# STM32F401CCU6.net
KiCad netlist of a schematic drawn in Altium Designer
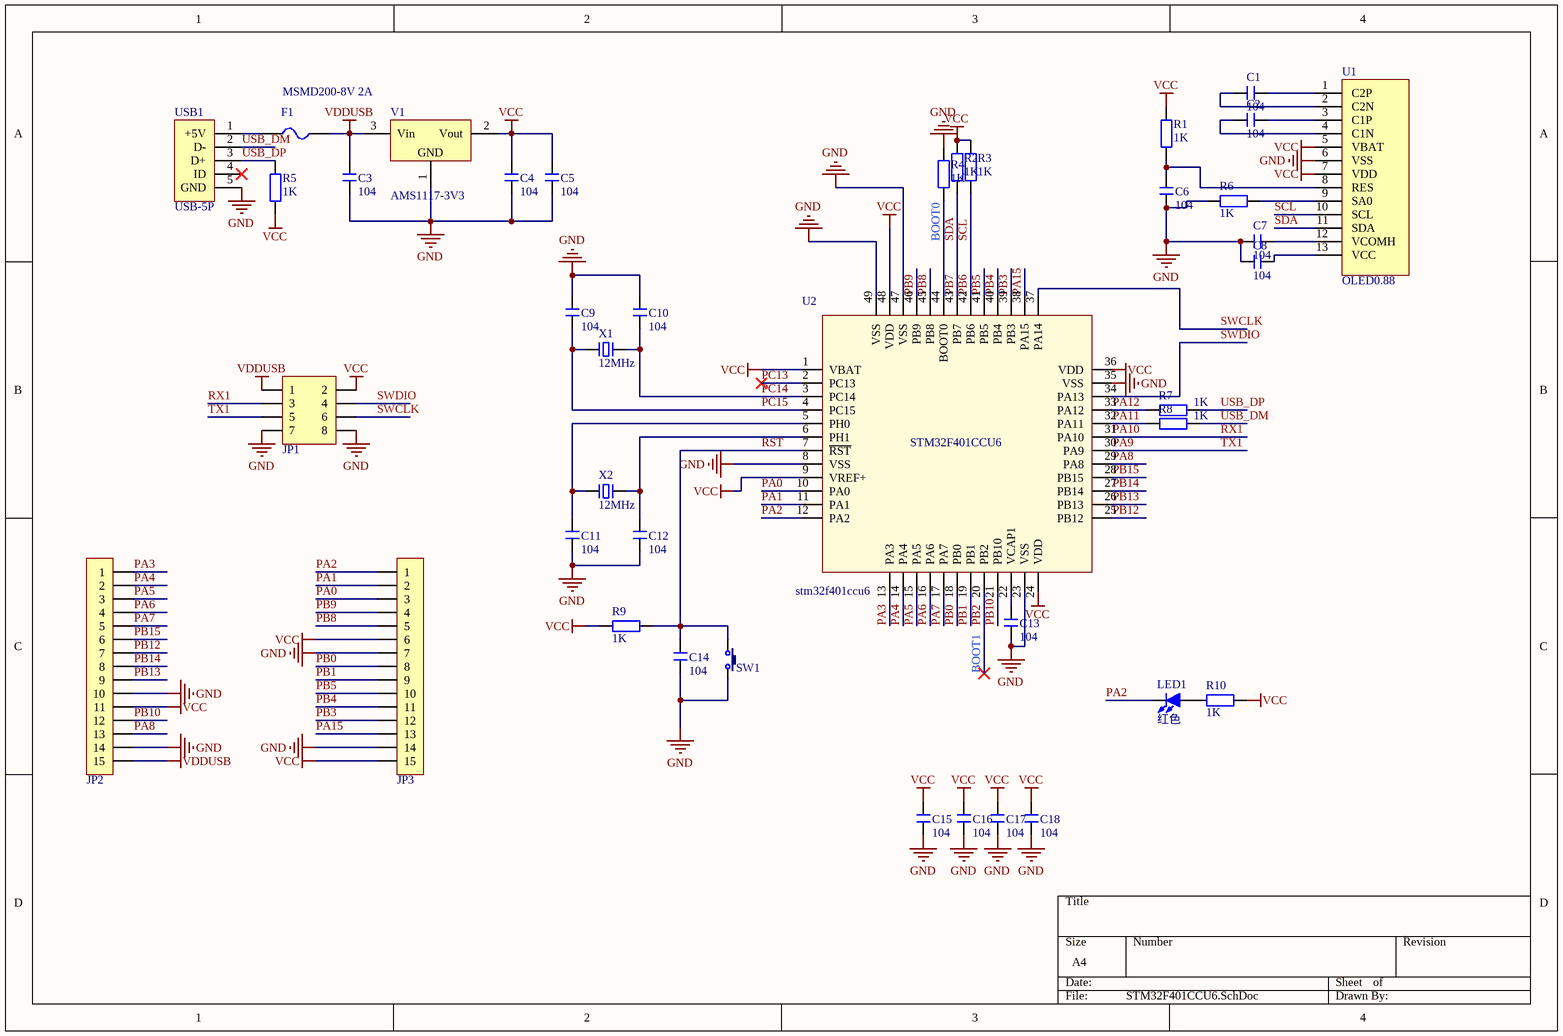
[diagram p0: STM32F401CCU6.SchDoc]

(export (version "E")
  (design (tool "Eeschema 10.0.6"))
  (components
    (comp (ref "C1")
      (value "104")
      (footprint "C 0603_L")
      (description "无极性贴片电容")
      (fields (field (name "版权归属") "源创客"))
      (libsource (lib "3.1   - 电阻-电容-电感") (part "C"))
    )
    (comp (ref "C2")
      (value "104")
      (footprint "C 0603_L")
      (description "无极性贴片电容")
      (fields (field (name "版权归属") "源创客"))
      (libsource (lib "3.1   - 电阻-电容-电感") (part "C"))
    )
    (comp (ref "C3")
      (value "104")
      (footprint "C 0805_L")
      (description "无极性贴片电容")
      (fields (field (name "版权归属") "源创客"))
      (libsource (lib "3.1   - 电阻-电容-电感") (part "C"))
    )
    (comp (ref "C4")
      (value "104")
      (footprint "C 0603_L")
      (description "无极性贴片电容")
      (fields (field (name "版权归属") "源创客"))
      (libsource (lib "3.1   - 电阻-电容-电感") (part "C"))
    )
    (comp (ref "C5")
      (value "104")
      (footprint "C 0603_L")
      (description "无极性贴片电容")
      (fields (field (name "版权归属") "源创客"))
      (libsource (lib "3.1   - 电阻-电容-电感") (part "C"))
    )
    (comp (ref "C6")
      (value "104")
      (footprint "C 0603_L")
      (description "无极性贴片电容")
      (fields (field (name "版权归属") "源创客"))
      (libsource (lib "3.1   - 电阻-电容-电感") (part "C"))
    )
    (comp (ref "C7")
      (value "104")
      (footprint "C 0603_L")
      (description "无极性贴片电容")
      (fields (field (name "版权归属") "源创客"))
      (libsource (lib "3.1   - 电阻-电容-电感") (part "C"))
    )
    (comp (ref "C8")
      (value "104")
      (footprint "C 0603_L")
      (description "无极性贴片电容")
      (fields (field (name "版权归属") "源创客"))
      (libsource (lib "3.1   - 电阻-电容-电感") (part "C"))
    )
    (comp (ref "C9")
      (value "104")
      (footprint "C 0603_L")
      (description "无极性贴片电容")
      (fields (field (name "版权归属") "源创客"))
      (libsource (lib "3.1   - 电阻-电容-电感") (part "C"))
    )
    (comp (ref "C10")
      (value "104")
      (footprint "C 0603_L")
      (description "无极性贴片电容")
      (fields (field (name "版权归属") "源创客"))
      (libsource (lib "3.1   - 电阻-电容-电感") (part "C"))
    )
    (comp (ref "C11")
      (value "104")
      (footprint "C 0603_L")
      (description "无极性贴片电容")
      (fields (field (name "版权归属") "源创客"))
      (libsource (lib "3.1   - 电阻-电容-电感") (part "C"))
    )
    (comp (ref "C12")
      (value "104")
      (footprint "C 0603_L")
      (description "无极性贴片电容")
      (fields (field (name "版权归属") "源创客"))
      (libsource (lib "3.1   - 电阻-电容-电感") (part "C"))
    )
    (comp (ref "C13")
      (value "104")
      (footprint "C 0603_L")
      (description "无极性贴片电容")
      (fields (field (name "版权归属") "源创客"))
      (libsource (lib "3.1   - 电阻-电容-电感") (part "C"))
    )
    (comp (ref "C14")
      (value "104")
      (footprint "C 0603_L")
      (description "无极性贴片电容")
      (fields (field (name "版权归属") "源创客"))
      (libsource (lib "3.1   - 电阻-电容-电感") (part "C"))
    )
    (comp (ref "C15")
      (value "104")
      (footprint "C 0603_L")
      (description "无极性贴片电容")
      (fields (field (name "版权归属") "源创客"))
      (libsource (lib "3.1   - 电阻-电容-电感") (part "C"))
    )
    (comp (ref "C16")
      (value "104")
      (footprint "C 0603_L")
      (description "无极性贴片电容")
      (fields (field (name "版权归属") "源创客"))
      (libsource (lib "3.1   - 电阻-电容-电感") (part "C"))
    )
    (comp (ref "C17")
      (value "104")
      (footprint "C 0603_L")
      (description "无极性贴片电容")
      (fields (field (name "版权归属") "源创客"))
      (libsource (lib "3.1   - 电阻-电容-电感") (part "C"))
    )
    (comp (ref "C18")
      (value "104")
      (footprint "C 0603_L")
      (description "无极性贴片电容")
      (fields (field (name "版权归属") "源创客"))
      (libsource (lib "3.1   - 电阻-电容-电感") (part "C"))
    )
    (comp (ref "F1")
      (value "MSMD200-8V 2A")
      (footprint "FU 0603")
      (description "贴片保险丝")
      (fields (field (name "版权归属") "源创客"))
      (libsource (lib "10.1 - 保险丝-晶振") (part "FU"))
    )
    (comp (ref "JP1")
      (value "Header 4X2")
      (footprint "HDR2.54-WI-2x4P")
      (description "4*2P接插件")
      (fields (field (name "版权归属") "源创客"))
      (libsource (lib "4.5   - 接插件-脚距2.54") (part "Header 4X2"))
    )
    (comp (ref "JP2")
      (value "HDR-1X15")
      (footprint "HDR2.54-LI-15P")
      (description "15P接插件")
      (fields (field (name "版权归属") "源创客"))
      (libsource (lib "4.5   - 接插件-脚距2.54") (part "Header 15"))
    )
    (comp (ref "JP3")
      (value "HDR-1X15")
      (footprint "HDR2.54-LI-15P")
      (description "15P接插件")
      (fields (field (name "版权归属") "源创客"))
      (libsource (lib "") (part "Header 15_1"))
    )
    (comp (ref "LED1")
      (value "红色")
      (footprint "LED 0603Y")
      (description "贴片LED")
      (fields (field (name "版权归属") "源创客"))
      (libsource (lib "9.1   - LED") (part "LED-SMD"))
    )
    (comp (ref "R1")
      (value "1K")
      (footprint "R 0603_L")
      (description "贴片电阻")
      (fields (field (name "版权归属") "源创客"))
      (libsource (lib "3.1   - 电阻-电容-电感") (part "R"))
    )
    (comp (ref "R2")
      (value "1K")
      (footprint "R 0603_L")
      (description "贴片电阻")
      (fields (field (name "版权归属") "源创客"))
      (libsource (lib "3.1   - 电阻-电容-电感") (part "R"))
    )
    (comp (ref "R3")
      (value "1K")
      (footprint "R 0603_L")
      (description "贴片电阻")
      (fields (field (name "版权归属") "源创客"))
      (libsource (lib "3.1   - 电阻-电容-电感") (part "R"))
    )
    (comp (ref "R4")
      (value "1K")
      (footprint "R 0603_L")
      (description "贴片电阻")
      (fields (field (name "版权归属") "源创客"))
      (libsource (lib "3.1   - 电阻-电容-电感") (part "R"))
    )
    (comp (ref "R5")
      (value "1K")
      (footprint "R 0603_L")
      (description "贴片电阻")
      (fields (field (name "版权归属") "源创客"))
      (libsource (lib "3.1   - 电阻-电容-电感") (part "R"))
    )
    (comp (ref "R6")
      (value "1K")
      (footprint "R 0603_L")
      (description "贴片电阻")
      (fields (field (name "版权归属") "源创客"))
      (libsource (lib "3.1   - 电阻-电容-电感") (part "R"))
    )
    (comp (ref "R7")
      (value "1K")
      (footprint "R 0603_L")
      (description "贴片电阻")
      (fields (field (name "版权归属") "源创客"))
      (libsource (lib "3.1   - 电阻-电容-电感") (part "R"))
    )
    (comp (ref "R8")
      (value "1K")
      (footprint "R 0603_L")
      (description "贴片电阻")
      (fields (field (name "版权归属") "源创客"))
      (libsource (lib "3.1   - 电阻-电容-电感") (part "R"))
    )
    (comp (ref "R9")
      (value "1K")
      (footprint "R 0603_L")
      (description "贴片电阻")
      (fields (field (name "版权归属") "源创客"))
      (libsource (lib "3.1   - 电阻-电容-电感") (part "R"))
    )
    (comp (ref "R10")
      (value "1K")
      (footprint "R 0603_L")
      (description "贴片电阻")
      (fields (field (name "版权归属") "源创客"))
      (libsource (lib "3.1   - 电阻-电容-电感") (part "R"))
    )
    (comp (ref "SW1")
      (value "3x6x5")
      (footprint "TSW 3*4*2-S-W")
      (description "3x6轻触开关")
      (fields (field (name "版权归属") "源创客"))
      (libsource (lib "5.1   - 按键-开关") (part "TSW 3x6"))
    )
    (comp (ref "U1")
      (value "OLED0.88")
      (footprint "OLED088")
      (description "0.88寸oled 128*32")
      (libsource (lib "9.2   - 显示器件") (part "OLED0.88"))
    )
    (comp (ref "U2")
      (value "stm32f401ccu6")
      (footprint "QFN48 7X7_L")
      (libsource (lib "GETWAY") (part "stm32f401ccu6"))
    )
    (comp (ref "USB1")
      (value "USB-5P")
      (footprint "USB-MICRO_A")
      (description "微型USB母座")
      (fields (field (name "版权归属") "源创客"))
      (libsource (lib "4.1   - 接口类") (part "USB-5P"))
    )
    (comp (ref "V1")
      (value "AMS1117-3V3")
      (footprint "SOT223_L")
      (description "三端稳压芯片")
      (fields (field (name "版权归属") "源创客"))
      (libsource (lib "1.3   - 电源类芯片") (part "AMS1117"))
    )
    (comp (ref "X1")
      (value "12MHz")
      (footprint "OSC 3215-2P")
      (description "2脚无源脚晶振")
      (fields (field (name "版权归属") "源创客"))
      (libsource (lib "10.1 - 保险丝-晶振") (part "XTAL-2P"))
    )
    (comp (ref "X2")
      (value "12MHz")
      (footprint "OSC 5032-2P")
      (description "2脚无源脚晶振")
      (fields (field (name "版权归属") "源创客"))
      (libsource (lib "10.1 - 保险丝-晶振") (part "XTAL-2P"))
    )
  )
  (nets
    (net (code "1") (name "/BOOT0") (class "Default")
      (node (ref "R4") (pin "1") (pinfunction "1_1") (pintype "passive"))
      (node (ref "U2") (pin "44") (pinfunction "BOOT0_44") (pintype "passive"))
    )
    (net (code "2") (name "/BOOT1") (class "Default")
      (node (ref "U2") (pin "20") (pinfunction "PB2_20") (pintype "passive+no_connect"))
    )
    (net (code "3") (name "/PA0") (class "Default")
      (node (ref "JP3") (pin "3") (pinfunction "3_3") (pintype "passive"))
      (node (ref "U2") (pin "10") (pinfunction "PA0_10") (pintype "passive"))
    )
    (net (code "4") (name "/PA1") (class "Default")
      (node (ref "JP3") (pin "2") (pinfunction "2_2") (pintype "passive"))
      (node (ref "U2") (pin "11") (pinfunction "PA1_11") (pintype "passive"))
    )
    (net (code "5") (name "/PA2") (class "Default")
      (node (ref "JP3") (pin "1") (pinfunction "1_1") (pintype "passive"))
      (node (ref "LED1") (pin "2") (pinfunction "K_2") (pintype "passive"))
      (node (ref "U2") (pin "12") (pinfunction "PA2_12") (pintype "passive"))
    )
    (net (code "6") (name "/PA3") (class "Default")
      (node (ref "JP2") (pin "1") (pinfunction "1_1") (pintype "passive"))
      (node (ref "U2") (pin "13") (pinfunction "PA3_13") (pintype "passive"))
    )
    (net (code "7") (name "/PA4") (class "Default")
      (node (ref "JP2") (pin "2") (pinfunction "2_2") (pintype "passive"))
      (node (ref "U2") (pin "14") (pinfunction "PA4_14") (pintype "passive"))
    )
    (net (code "8") (name "/PA5") (class "Default")
      (node (ref "JP2") (pin "3") (pinfunction "3_3") (pintype "passive"))
      (node (ref "U2") (pin "15") (pinfunction "PA5_15") (pintype "passive"))
    )
    (net (code "9") (name "/PA6") (class "Default")
      (node (ref "JP2") (pin "4") (pinfunction "4_4") (pintype "passive"))
      (node (ref "U2") (pin "16") (pinfunction "PA6_16") (pintype "passive"))
    )
    (net (code "10") (name "/PA7") (class "Default")
      (node (ref "JP2") (pin "5") (pinfunction "5_5") (pintype "passive"))
      (node (ref "U2") (pin "17") (pinfunction "PA7_17") (pintype "passive"))
    )
    (net (code "11") (name "/PA8") (class "Default")
      (node (ref "JP2") (pin "13") (pinfunction "13_13") (pintype "passive"))
      (node (ref "U2") (pin "29") (pinfunction "PA8_29") (pintype "passive"))
    )
    (net (code "12") (name "/PA9") (class "Default")
      (node (ref "JP1") (pin "5") (pinfunction "5_5") (pintype "passive"))
      (node (ref "U2") (pin "30") (pinfunction "PA9_30") (pintype "passive"))
    )
    (net (code "13") (name "/PA10") (class "Default")
      (node (ref "JP1") (pin "3") (pinfunction "3_3") (pintype "passive"))
      (node (ref "U2") (pin "31") (pinfunction "PA10_31") (pintype "passive"))
    )
    (net (code "14") (name "/PA11") (class "Default")
      (node (ref "R8") (pin "1") (pinfunction "1_1") (pintype "passive"))
      (node (ref "U2") (pin "32") (pinfunction "PA11_32") (pintype "passive"))
    )
    (net (code "15") (name "/PA12") (class "Default")
      (node (ref "R7") (pin "1") (pinfunction "1_1") (pintype "passive"))
      (node (ref "U2") (pin "33") (pinfunction "PA12_33") (pintype "passive"))
    )
    (net (code "16") (name "/PA15") (class "Default")
      (node (ref "JP3") (pin "13") (pinfunction "13_13") (pintype "passive"))
      (node (ref "U2") (pin "38") (pinfunction "PA15_38") (pintype "passive"))
    )
    (net (code "17") (name "/PB0") (class "Default")
      (node (ref "JP3") (pin "8") (pinfunction "8_8") (pintype "passive"))
      (node (ref "U2") (pin "18") (pinfunction "PB0_18") (pintype "passive"))
    )
    (net (code "18") (name "/PB1") (class "Default")
      (node (ref "JP3") (pin "9") (pinfunction "9_9") (pintype "passive"))
      (node (ref "U2") (pin "19") (pinfunction "PB1_19") (pintype "passive"))
    )
    (net (code "19") (name "/PB3") (class "Default")
      (node (ref "JP3") (pin "12") (pinfunction "12_12") (pintype "passive"))
      (node (ref "U2") (pin "39") (pinfunction "PB3_39") (pintype "passive"))
    )
    (net (code "20") (name "/PB4") (class "Default")
      (node (ref "JP3") (pin "11") (pinfunction "11_11") (pintype "passive"))
      (node (ref "U2") (pin "40") (pinfunction "PB4_40") (pintype "passive"))
    )
    (net (code "21") (name "/PB5") (class "Default")
      (node (ref "JP3") (pin "10") (pinfunction "10_10") (pintype "passive"))
      (node (ref "U2") (pin "41") (pinfunction "PB5_41") (pintype "passive"))
    )
    (net (code "22") (name "/PB6") (class "Default")
      (node (ref "R3") (pin "1") (pinfunction "1_1") (pintype "passive"))
      (node (ref "U1") (pin "10") (pinfunction "SCL_10") (pintype "passive"))
      (node (ref "U2") (pin "42") (pinfunction "PB6_42") (pintype "passive"))
    )
    (net (code "23") (name "/PB7") (class "Default")
      (node (ref "R2") (pin "1") (pinfunction "1_1") (pintype "passive"))
      (node (ref "U1") (pin "11") (pinfunction "SDA_11") (pintype "passive"))
      (node (ref "U2") (pin "43") (pinfunction "PB7_43") (pintype "passive"))
    )
    (net (code "24") (name "/PB8") (class "Default")
      (node (ref "JP3") (pin "5") (pinfunction "5_5") (pintype "passive"))
      (node (ref "U2") (pin "45") (pinfunction "PB8_45") (pintype "passive"))
    )
    (net (code "25") (name "/PB9") (class "Default")
      (node (ref "JP3") (pin "4") (pinfunction "4_4") (pintype "passive"))
      (node (ref "U2") (pin "46") (pinfunction "PB9_46") (pintype "passive"))
    )
    (net (code "26") (name "/PB10") (class "Default")
      (node (ref "JP2") (pin "12") (pinfunction "12_12") (pintype "passive"))
      (node (ref "U2") (pin "21") (pinfunction "PB10_21") (pintype "passive"))
    )
    (net (code "27") (name "/PB12") (class "Default")
      (node (ref "JP2") (pin "7") (pinfunction "7_7") (pintype "passive"))
      (node (ref "U2") (pin "25") (pinfunction "PB12_25") (pintype "passive"))
    )
    (net (code "28") (name "/PB13") (class "Default")
      (node (ref "JP2") (pin "9") (pinfunction "9_9") (pintype "passive"))
      (node (ref "U2") (pin "26") (pinfunction "PB13_26") (pintype "passive"))
    )
    (net (code "29") (name "/PB14") (class "Default")
      (node (ref "JP2") (pin "8") (pinfunction "8_8") (pintype "passive"))
      (node (ref "U2") (pin "27") (pinfunction "PB14_27") (pintype "passive"))
    )
    (net (code "30") (name "/PB15") (class "Default")
      (node (ref "JP2") (pin "6") (pinfunction "6_6") (pintype "passive"))
      (node (ref "U2") (pin "28") (pinfunction "PB15_28") (pintype "passive"))
    )
    (net (code "31") (name "/PC13") (class "Default")
      (node (ref "U2") (pin "2") (pinfunction "PC13_2") (pintype "passive+no_connect"))
    )
    (net (code "32") (name "/PC14") (class "Default")
      (node (ref "C10") (pin "1") (pinfunction "1_1") (pintype "passive"))
      (node (ref "U2") (pin "3") (pinfunction "PC14_3") (pintype "passive"))
      (node (ref "X1") (pin "2") (pinfunction "2_2") (pintype "passive"))
    )
    (net (code "33") (name "/PC15") (class "Default")
      (node (ref "C9") (pin "1") (pinfunction "1_1") (pintype "passive"))
      (node (ref "U2") (pin "4") (pinfunction "PC15_4") (pintype "passive"))
      (node (ref "X1") (pin "1") (pinfunction "1_1") (pintype "passive"))
    )
    (net (code "34") (name "/RST") (class "Default")
      (node (ref "C14") (pin "2") (pinfunction "2_2") (pintype "passive"))
      (node (ref "R9") (pin "2") (pinfunction "2_2") (pintype "passive"))
      (node (ref "SW1") (pin "1") (pinfunction "1_1") (pintype "passive"))
      (node (ref "U2") (pin "7") (pinfunction "~{RST}_7") (pintype "passive"))
    )
    (net (code "35") (name "/SWCLK") (class "Default")
      (node (ref "JP1") (pin "6") (pinfunction "6_6") (pintype "passive"))
      (node (ref "U2") (pin "37") (pinfunction "PA14_37") (pintype "passive"))
    )
    (net (code "36") (name "/SWDIO") (class "Default")
      (node (ref "JP1") (pin "4") (pinfunction "4_4") (pintype "passive"))
      (node (ref "U2") (pin "34") (pinfunction "PA13_34") (pintype "passive"))
    )
    (net (code "37") (name "/USB_DM") (class "Default")
      (node (ref "R8") (pin "2") (pinfunction "2_2") (pintype "passive"))
      (node (ref "USB1") (pin "2") (pinfunction "D-_2") (pintype "passive"))
    )
    (net (code "38") (name "/USB_DP") (class "Default")
      (node (ref "R5") (pin "2") (pinfunction "2_2") (pintype "passive"))
      (node (ref "R7") (pin "2") (pinfunction "2_2") (pintype "passive"))
      (node (ref "USB1") (pin "3") (pinfunction "D+_3") (pintype "passive"))
    )
    (net (code "39") (name "GND") (class "Default")
      (node (ref "C10") (pin "2") (pinfunction "2_2") (pintype "passive"))
      (node (ref "C11") (pin "1") (pinfunction "1_1") (pintype "passive"))
      (node (ref "C12") (pin "1") (pinfunction "1_1") (pintype "passive"))
      (node (ref "C13") (pin "1") (pinfunction "1_1") (pintype "passive"))
      (node (ref "C14") (pin "1") (pinfunction "1_1") (pintype "passive"))
      (node (ref "C15") (pin "1") (pinfunction "1_1") (pintype "passive"))
      (node (ref "C16") (pin "1") (pinfunction "1_1") (pintype "passive"))
      (node (ref "C17") (pin "1") (pinfunction "1_1") (pintype "passive"))
      (node (ref "C18") (pin "1") (pinfunction "1_1") (pintype "passive"))
      (node (ref "C3") (pin "1") (pinfunction "1_1") (pintype "passive"))
      (node (ref "C4") (pin "1") (pinfunction "1_1") (pintype "passive"))
      (node (ref "C5") (pin "1") (pinfunction "1_1") (pintype "passive"))
      (node (ref "C6") (pin "1") (pinfunction "1_1") (pintype "passive"))
      (node (ref "C7") (pin "1") (pinfunction "1_1") (pintype "passive"))
      (node (ref "C8") (pin "1") (pinfunction "1_1") (pintype "passive"))
      (node (ref "C9") (pin "2") (pinfunction "2_2") (pintype "passive"))
      (node (ref "JP1") (pin "7") (pinfunction "7_7") (pintype "passive"))
      (node (ref "JP1") (pin "8") (pinfunction "8_8") (pintype "passive"))
      (node (ref "JP2") (pin "10") (pinfunction "10_10") (pintype "passive"))
      (node (ref "JP2") (pin "14") (pinfunction "14_14") (pintype "passive"))
      (node (ref "JP3") (pin "14") (pinfunction "14_14") (pintype "passive"))
      (node (ref "JP3") (pin "7") (pinfunction "7_7") (pintype "passive"))
      (node (ref "R4") (pin "2") (pinfunction "2_2") (pintype "passive"))
      (node (ref "R6") (pin "1") (pinfunction "1_1") (pintype "passive"))
      (node (ref "SW1") (pin "2") (pinfunction "2_2") (pintype "passive"))
      (node (ref "U1") (pin "6") (pinfunction "VSS_6") (pintype "passive"))
      (node (ref "U2") (pin "23") (pinfunction "VSS_23") (pintype "passive"))
      (node (ref "U2") (pin "35") (pinfunction "VSS_35") (pintype "passive"))
      (node (ref "U2") (pin "47") (pinfunction "VSS_47") (pintype "passive"))
      (node (ref "U2") (pin "49") (pinfunction "VSS_49") (pintype "passive"))
      (node (ref "U2") (pin "8") (pinfunction "VSS_8") (pintype "passive"))
      (node (ref "USB1") (pin "5") (pinfunction "GND_5") (pintype "passive"))
      (node (ref "V1") (pin "1") (pinfunction "GND_1") (pintype "passive"))
    )
    (net (code "40") (name "Net-(LED1-A)") (class "Default")
      (node (ref "LED1") (pin "1") (pinfunction "A_1") (pintype "passive"))
      (node (ref "R10") (pin "1") (pinfunction "1_1") (pintype "passive"))
    )
    (net (code "41") (name "Net-(U1-C1N)") (class "Default")
      (node (ref "C2") (pin "1") (pinfunction "1_1") (pintype "passive"))
      (node (ref "U1") (pin "4") (pinfunction "C1N_4") (pintype "passive"))
    )
    (net (code "42") (name "Net-(U1-C1P)") (class "Default")
      (node (ref "C2") (pin "2") (pinfunction "2_2") (pintype "passive"))
      (node (ref "U1") (pin "3") (pinfunction "C1P_3") (pintype "passive"))
    )
    (net (code "43") (name "Net-(U1-C2N)") (class "Default")
      (node (ref "C1") (pin "1") (pinfunction "1_1") (pintype "passive"))
      (node (ref "U1") (pin "2") (pinfunction "C2N_2") (pintype "passive"))
    )
    (net (code "44") (name "Net-(U1-C2P)") (class "Default")
      (node (ref "C1") (pin "2") (pinfunction "2_2") (pintype "passive"))
      (node (ref "U1") (pin "1") (pinfunction "C2P_1") (pintype "passive"))
    )
    (net (code "45") (name "Net-(U1-RES)") (class "Default")
      (node (ref "C6") (pin "2") (pinfunction "2_2") (pintype "passive"))
      (node (ref "R1") (pin "2") (pinfunction "2_2") (pintype "passive"))
      (node (ref "U1") (pin "8") (pinfunction "RES_8") (pintype "passive"))
    )
    (net (code "46") (name "Net-(U1-SA0)") (class "Default")
      (node (ref "R6") (pin "2") (pinfunction "2_2") (pintype "passive"))
      (node (ref "U1") (pin "9") (pinfunction "SA0_9") (pintype "passive"))
    )
    (net (code "47") (name "Net-(U1-VCC)") (class "Default")
      (node (ref "C8") (pin "2") (pinfunction "2_2") (pintype "passive"))
      (node (ref "U1") (pin "13") (pinfunction "VCC_13") (pintype "passive"))
    )
    (net (code "48") (name "Net-(U1-VCOMH)") (class "Default")
      (node (ref "C7") (pin "2") (pinfunction "2_2") (pintype "passive"))
      (node (ref "U1") (pin "12") (pinfunction "VCOMH_12") (pintype "passive"))
    )
    (net (code "49") (name "Net-(U2-PH0)") (class "Default")
      (node (ref "C11") (pin "2") (pinfunction "2_2") (pintype "passive"))
      (node (ref "U2") (pin "5") (pinfunction "PH0_5") (pintype "passive"))
      (node (ref "X2") (pin "1") (pinfunction "1_1") (pintype "passive"))
    )
    (net (code "50") (name "Net-(U2-PH1)") (class "Default")
      (node (ref "C12") (pin "2") (pinfunction "2_2") (pintype "passive"))
      (node (ref "U2") (pin "6") (pinfunction "PH1_6") (pintype "passive"))
      (node (ref "X2") (pin "2") (pinfunction "2_2") (pintype "passive"))
    )
    (net (code "51") (name "Net-(U2-VCAP1)") (class "Default")
      (node (ref "C13") (pin "2") (pinfunction "2_2") (pintype "passive"))
      (node (ref "U2") (pin "22") (pinfunction "VCAP1_22") (pintype "passive"))
    )
    (net (code "52") (name "Net-(USB1-+5V)") (class "Default")
      (node (ref "F1") (pin "1") (pinfunction "1_1") (pintype "passive"))
      (node (ref "USB1") (pin "1") (pinfunction "+5V_1") (pintype "passive"))
    )
    (net (code "53") (name "VCC") (class "Default")
      (node (ref "C15") (pin "2") (pinfunction "2_2") (pintype "passive"))
      (node (ref "C16") (pin "2") (pinfunction "2_2") (pintype "passive"))
      (node (ref "C17") (pin "2") (pinfunction "2_2") (pintype "passive"))
      (node (ref "C18") (pin "2") (pinfunction "2_2") (pintype "passive"))
      (node (ref "C4") (pin "2") (pinfunction "2_2") (pintype "passive"))
      (node (ref "C5") (pin "2") (pinfunction "2_2") (pintype "passive"))
      (node (ref "JP1") (pin "2") (pinfunction "2_2") (pintype "passive"))
      (node (ref "JP2") (pin "11") (pinfunction "11_11") (pintype "passive"))
      (node (ref "JP3") (pin "15") (pinfunction "15_15") (pintype "passive"))
      (node (ref "JP3") (pin "6") (pinfunction "6_6") (pintype "passive"))
      (node (ref "R1") (pin "1") (pinfunction "1_1") (pintype "passive"))
      (node (ref "R10") (pin "2") (pinfunction "2_2") (pintype "passive"))
      (node (ref "R2") (pin "2") (pinfunction "2_2") (pintype "passive"))
      (node (ref "R3") (pin "2") (pinfunction "2_2") (pintype "passive"))
      (node (ref "R5") (pin "1") (pinfunction "1_1") (pintype "passive"))
      (node (ref "R9") (pin "1") (pinfunction "1_1") (pintype "passive"))
      (node (ref "U1") (pin "5") (pinfunction "VBAT_5") (pintype "passive"))
      (node (ref "U1") (pin "7") (pinfunction "VDD_7") (pintype "passive"))
      (node (ref "U2") (pin "1") (pinfunction "VBAT_1") (pintype "passive"))
      (node (ref "U2") (pin "24") (pinfunction "VDD_24") (pintype "passive"))
      (node (ref "U2") (pin "36") (pinfunction "VDD_36") (pintype "passive"))
      (node (ref "U2") (pin "48") (pinfunction "VDD_48") (pintype "passive"))
      (node (ref "U2") (pin "9") (pinfunction "VREF+_9") (pintype "passive"))
      (node (ref "V1") (pin "2") (pinfunction "Vout_2") (pintype "passive"))
    )
    (net (code "54") (name "VDDUSB") (class "Default")
      (node (ref "C3") (pin "2") (pinfunction "2_2") (pintype "passive"))
      (node (ref "F1") (pin "2") (pinfunction "2_2") (pintype "passive"))
      (node (ref "JP1") (pin "1") (pinfunction "1_1") (pintype "passive"))
      (node (ref "JP2") (pin "15") (pinfunction "15_15") (pintype "passive"))
      (node (ref "V1") (pin "3") (pinfunction "Vin_3") (pintype "passive"))
    )
    (net (code "55") (name "unconnected-(USB1-ID-Pad4)") (class "Default")
      (node (ref "USB1") (pin "4") (pinfunction "ID_4") (pintype "passive+no_connect"))
    )
  )
)
